# e-Tapperhandpiece30.net
KiCad netlist of a schematic drawn in EAGLE
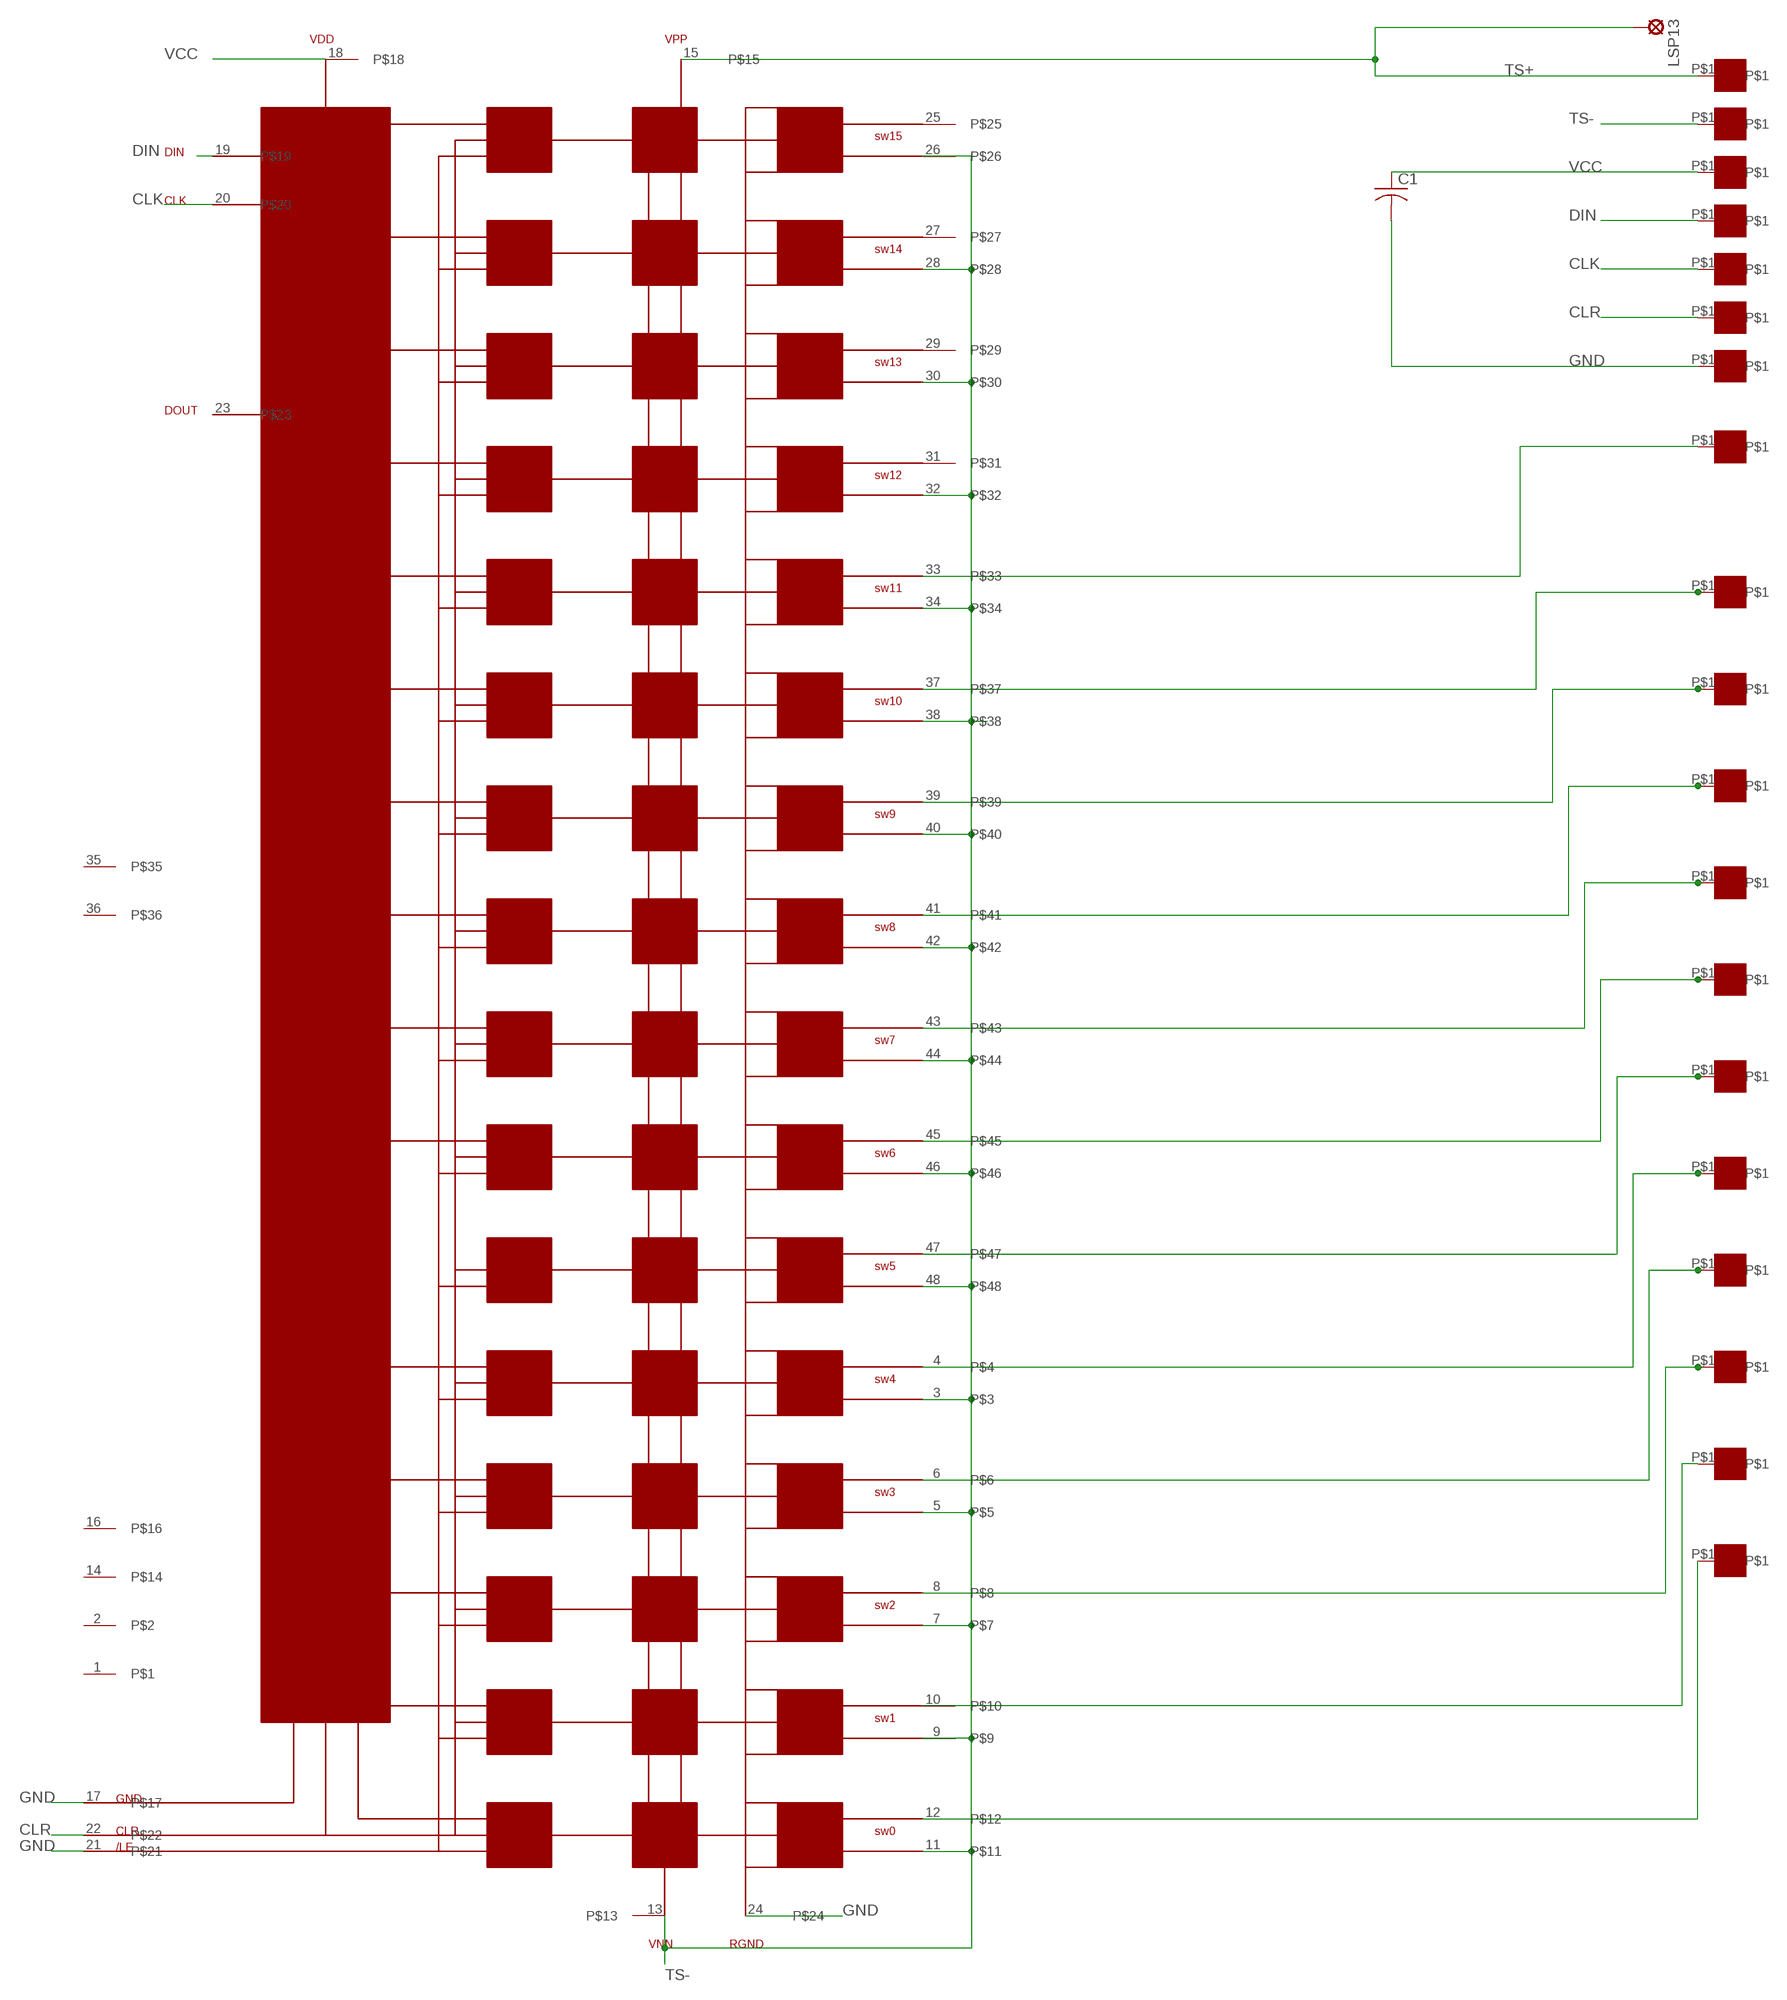
[diagram p0: schematic, sheet 1]

(export (version "E")
  (design (tool "Eeschema 10.0.6"))
  (components
    (comp (ref "C1")
      (value "C-USC0805")
      (footprint "eagle-import:C0805")
      (libsource (lib "eagle-import") (part "C-USC0805"))
    )
    (comp (ref "LSP13")
      (value "SE11")
      (footprint "eagle-import:SE11")
      (libsource (lib "eagle-import") (part "SE11"))
    )
    (comp (ref "TSP1")
      (value "ET1")
      (footprint "eagle-import:ET1")
      (libsource (lib "eagle-import") (part "ET1"))
    )
    (comp (ref "TSP2")
      (value "ET1")
      (footprint "eagle-import:ET1")
      (libsource (lib "eagle-import") (part "ET1"))
    )
    (comp (ref "TSP3")
      (value "ET1")
      (footprint "eagle-import:ET1")
      (libsource (lib "eagle-import") (part "ET1"))
    )
    (comp (ref "TSP4")
      (value "ET1")
      (footprint "eagle-import:ET1")
      (libsource (lib "eagle-import") (part "ET1"))
    )
    (comp (ref "TSP5")
      (value "ET1")
      (footprint "eagle-import:ET1")
      (libsource (lib "eagle-import") (part "ET1"))
    )
    (comp (ref "TSP6")
      (value "ET1")
      (footprint "eagle-import:ET1")
      (libsource (lib "eagle-import") (part "ET1"))
    )
    (comp (ref "TSP7")
      (value "ET1")
      (footprint "eagle-import:ET1")
      (libsource (lib "eagle-import") (part "ET1"))
    )
    (comp (ref "TSP8")
      (value "ET1")
      (footprint "eagle-import:ET1")
      (libsource (lib "eagle-import") (part "ET1"))
    )
    (comp (ref "TSP9")
      (value "ET1")
      (footprint "eagle-import:ET1")
      (libsource (lib "eagle-import") (part "ET1"))
    )
    (comp (ref "TSP10")
      (value "ET1")
      (footprint "eagle-import:ET1")
      (libsource (lib "eagle-import") (part "ET1"))
    )
    (comp (ref "TSP11")
      (value "ET1")
      (footprint "eagle-import:ET1")
      (libsource (lib "eagle-import") (part "ET1"))
    )
    (comp (ref "TSP12")
      (value "ET1")
      (footprint "eagle-import:ET1")
      (libsource (lib "eagle-import") (part "ET1"))
    )
    (comp (ref "TSP13")
      (value "ET1")
      (footprint "eagle-import:ET1")
      (libsource (lib "eagle-import") (part "ET1"))
    )
    (comp (ref "TSP14")
      (value "ET1")
      (footprint "eagle-import:ET1")
      (libsource (lib "eagle-import") (part "ET1"))
    )
    (comp (ref "TSP15")
      (value "ET1")
      (footprint "eagle-import:ET1")
      (libsource (lib "eagle-import") (part "ET1"))
    )
    (comp (ref "TSP16")
      (value "ET1")
      (footprint "eagle-import:ET1")
      (libsource (lib "eagle-import") (part "ET1"))
    )
    (comp (ref "TSP17")
      (value "ET1")
      (footprint "eagle-import:ET1")
      (libsource (lib "eagle-import") (part "ET1"))
    )
    (comp (ref "TSP18")
      (value "ET1")
      (footprint "eagle-import:ET1")
      (libsource (lib "eagle-import") (part "ET1"))
    )
    (comp (ref "TSP19")
      (value "ET1")
      (footprint "eagle-import:ET1")
      (libsource (lib "eagle-import") (part "ET1"))
    )
    (comp (ref "U$1")
      (value "CPC7701")
      (footprint "eagle-import:LQFP48")
      (libsource (lib "eagle-import") (part "CPC7701"))
    )
  )
  (nets
    (net (code "1") (name "/CLK") (class "Default")
      (node (ref "TSP17") (pin "P$1") (pinfunction "P$1_P$1") (pintype "bidirectional"))
      (node (ref "U$1") (pin "20") (pinfunction "P$20_20") (pintype "bidirectional"))
    )
    (net (code "2") (name "/CLR") (class "Default")
      (node (ref "TSP18") (pin "P$1") (pinfunction "P$1_P$1") (pintype "bidirectional"))
      (node (ref "U$1") (pin "22") (pinfunction "P$22_22") (pintype "bidirectional"))
    )
    (net (code "3") (name "/DIN") (class "Default")
      (node (ref "TSP16") (pin "P$1") (pinfunction "P$1_P$1") (pintype "bidirectional"))
      (node (ref "U$1") (pin "19") (pinfunction "P$19_19") (pintype "bidirectional"))
    )
    (net (code "4") (name "/GND") (class "Default")
      (node (ref "C1") (pin "2") (pinfunction "2_2") (pintype "passive"))
      (node (ref "TSP19") (pin "P$1") (pinfunction "P$1_P$1") (pintype "bidirectional"))
      (node (ref "U$1") (pin "17") (pinfunction "P$17_17") (pintype "bidirectional"))
      (node (ref "U$1") (pin "21") (pinfunction "P$21_21") (pintype "bidirectional"))
      (node (ref "U$1") (pin "24") (pinfunction "P$24_24") (pintype "bidirectional"))
    )
    (net (code "5") (name "/TS+") (class "Default")
      (node (ref "LSP13") (pin "MP") (pinfunction "MP_MP") (pintype "passive"))
      (node (ref "TSP13") (pin "P$1") (pinfunction "P$1_P$1") (pintype "bidirectional"))
      (node (ref "U$1") (pin "15") (pinfunction "P$15_15") (pintype "bidirectional"))
    )
    (net (code "6") (name "/TS-") (class "Default")
      (node (ref "TSP14") (pin "P$1") (pinfunction "P$1_P$1") (pintype "bidirectional"))
      (node (ref "U$1") (pin "11") (pinfunction "P$11_11") (pintype "bidirectional"))
      (node (ref "U$1") (pin "13") (pinfunction "P$13_13") (pintype "bidirectional"))
      (node (ref "U$1") (pin "26") (pinfunction "P$26_26") (pintype "bidirectional"))
      (node (ref "U$1") (pin "28") (pinfunction "P$28_28") (pintype "bidirectional"))
      (node (ref "U$1") (pin "3") (pinfunction "P$3_3") (pintype "bidirectional"))
      (node (ref "U$1") (pin "30") (pinfunction "P$30_30") (pintype "bidirectional"))
      (node (ref "U$1") (pin "32") (pinfunction "P$32_32") (pintype "bidirectional"))
      (node (ref "U$1") (pin "34") (pinfunction "P$34_34") (pintype "bidirectional"))
      (node (ref "U$1") (pin "38") (pinfunction "P$38_38") (pintype "bidirectional"))
      (node (ref "U$1") (pin "40") (pinfunction "P$40_40") (pintype "bidirectional"))
      (node (ref "U$1") (pin "42") (pinfunction "P$42_42") (pintype "bidirectional"))
      (node (ref "U$1") (pin "44") (pinfunction "P$44_44") (pintype "bidirectional"))
      (node (ref "U$1") (pin "46") (pinfunction "P$46_46") (pintype "bidirectional"))
      (node (ref "U$1") (pin "48") (pinfunction "P$48_48") (pintype "bidirectional"))
      (node (ref "U$1") (pin "5") (pinfunction "P$5_5") (pintype "bidirectional"))
      (node (ref "U$1") (pin "7") (pinfunction "P$7_7") (pintype "bidirectional"))
      (node (ref "U$1") (pin "9") (pinfunction "P$9_9") (pintype "bidirectional"))
    )
    (net (code "7") (name "/VCC") (class "Default")
      (node (ref "C1") (pin "1") (pinfunction "1_1") (pintype "passive"))
      (node (ref "TSP15") (pin "P$1") (pinfunction "P$1_P$1") (pintype "bidirectional"))
      (node (ref "U$1") (pin "18") (pinfunction "P$18_18") (pintype "bidirectional"))
    )
    (net (code "8") (name "Net-(U$1-P$4)") (class "Default")
      (node (ref "TSP8") (pin "P$1") (pinfunction "P$1_P$1") (pintype "bidirectional"))
      (node (ref "U$1") (pin "4") (pinfunction "P$4_4") (pintype "bidirectional"))
    )
    (net (code "9") (name "Net-(U$1-P$6)") (class "Default")
      (node (ref "TSP9") (pin "P$1") (pinfunction "P$1_P$1") (pintype "bidirectional"))
      (node (ref "U$1") (pin "6") (pinfunction "P$6_6") (pintype "bidirectional"))
    )
    (net (code "10") (name "Net-(U$1-P$8)") (class "Default")
      (node (ref "TSP10") (pin "P$1") (pinfunction "P$1_P$1") (pintype "bidirectional"))
      (node (ref "U$1") (pin "8") (pinfunction "P$8_8") (pintype "bidirectional"))
    )
    (net (code "11") (name "Net-(U$1-P$10)") (class "Default")
      (node (ref "TSP11") (pin "P$1") (pinfunction "P$1_P$1") (pintype "bidirectional"))
      (node (ref "U$1") (pin "10") (pinfunction "P$10_10") (pintype "bidirectional"))
    )
    (net (code "12") (name "Net-(U$1-P$12)") (class "Default")
      (node (ref "TSP12") (pin "P$1") (pinfunction "P$1_P$1") (pintype "bidirectional"))
      (node (ref "U$1") (pin "12") (pinfunction "P$12_12") (pintype "bidirectional"))
    )
    (net (code "13") (name "Net-(U$1-P$33)") (class "Default")
      (node (ref "TSP1") (pin "P$1") (pinfunction "P$1_P$1") (pintype "bidirectional"))
      (node (ref "U$1") (pin "33") (pinfunction "P$33_33") (pintype "bidirectional"))
    )
    (net (code "14") (name "Net-(U$1-P$37)") (class "Default")
      (node (ref "TSP2") (pin "P$1") (pinfunction "P$1_P$1") (pintype "bidirectional"))
      (node (ref "U$1") (pin "37") (pinfunction "P$37_37") (pintype "bidirectional"))
    )
    (net (code "15") (name "Net-(U$1-P$39)") (class "Default")
      (node (ref "TSP3") (pin "P$1") (pinfunction "P$1_P$1") (pintype "bidirectional"))
      (node (ref "U$1") (pin "39") (pinfunction "P$39_39") (pintype "bidirectional"))
    )
    (net (code "16") (name "Net-(U$1-P$41)") (class "Default")
      (node (ref "TSP4") (pin "P$1") (pinfunction "P$1_P$1") (pintype "bidirectional"))
      (node (ref "U$1") (pin "41") (pinfunction "P$41_41") (pintype "bidirectional"))
    )
    (net (code "17") (name "Net-(U$1-P$43)") (class "Default")
      (node (ref "TSP5") (pin "P$1") (pinfunction "P$1_P$1") (pintype "bidirectional"))
      (node (ref "U$1") (pin "43") (pinfunction "P$43_43") (pintype "bidirectional"))
    )
    (net (code "18") (name "Net-(U$1-P$45)") (class "Default")
      (node (ref "TSP6") (pin "P$1") (pinfunction "P$1_P$1") (pintype "bidirectional"))
      (node (ref "U$1") (pin "45") (pinfunction "P$45_45") (pintype "bidirectional"))
    )
    (net (code "19") (name "Net-(U$1-P$47)") (class "Default")
      (node (ref "TSP7") (pin "P$1") (pinfunction "P$1_P$1") (pintype "bidirectional"))
      (node (ref "U$1") (pin "47") (pinfunction "P$47_47") (pintype "bidirectional"))
    )
    (net (code "20") (name "unconnected-(U$1-P$1-Pad1)") (class "Default")
      (node (ref "U$1") (pin "1") (pinfunction "P$1_1") (pintype "bidirectional"))
    )
    (net (code "21") (name "unconnected-(U$1-P$2-Pad2)") (class "Default")
      (node (ref "U$1") (pin "2") (pinfunction "P$2_2") (pintype "bidirectional"))
    )
    (net (code "22") (name "unconnected-(U$1-P$14-Pad14)") (class "Default")
      (node (ref "U$1") (pin "14") (pinfunction "P$14_14") (pintype "bidirectional"))
    )
    (net (code "23") (name "unconnected-(U$1-P$16-Pad16)") (class "Default")
      (node (ref "U$1") (pin "16") (pinfunction "P$16_16") (pintype "bidirectional"))
    )
    (net (code "24") (name "unconnected-(U$1-P$23-Pad23)") (class "Default")
      (node (ref "U$1") (pin "23") (pinfunction "P$23_23") (pintype "bidirectional"))
    )
    (net (code "25") (name "unconnected-(U$1-P$25-Pad25)") (class "Default")
      (node (ref "U$1") (pin "25") (pinfunction "P$25_25") (pintype "bidirectional"))
    )
    (net (code "26") (name "unconnected-(U$1-P$27-Pad27)") (class "Default")
      (node (ref "U$1") (pin "27") (pinfunction "P$27_27") (pintype "bidirectional"))
    )
    (net (code "27") (name "unconnected-(U$1-P$29-Pad29)") (class "Default")
      (node (ref "U$1") (pin "29") (pinfunction "P$29_29") (pintype "bidirectional"))
    )
    (net (code "28") (name "unconnected-(U$1-P$31-Pad31)") (class "Default")
      (node (ref "U$1") (pin "31") (pinfunction "P$31_31") (pintype "bidirectional"))
    )
    (net (code "29") (name "unconnected-(U$1-P$35-Pad35)") (class "Default")
      (node (ref "U$1") (pin "35") (pinfunction "P$35_35") (pintype "bidirectional"))
    )
    (net (code "30") (name "unconnected-(U$1-P$36-Pad36)") (class "Default")
      (node (ref "U$1") (pin "36") (pinfunction "P$36_36") (pintype "bidirectional"))
    )
  )
)
